# halfBridge.net
KiCad netlist of a schematic drawn in Altium Designer
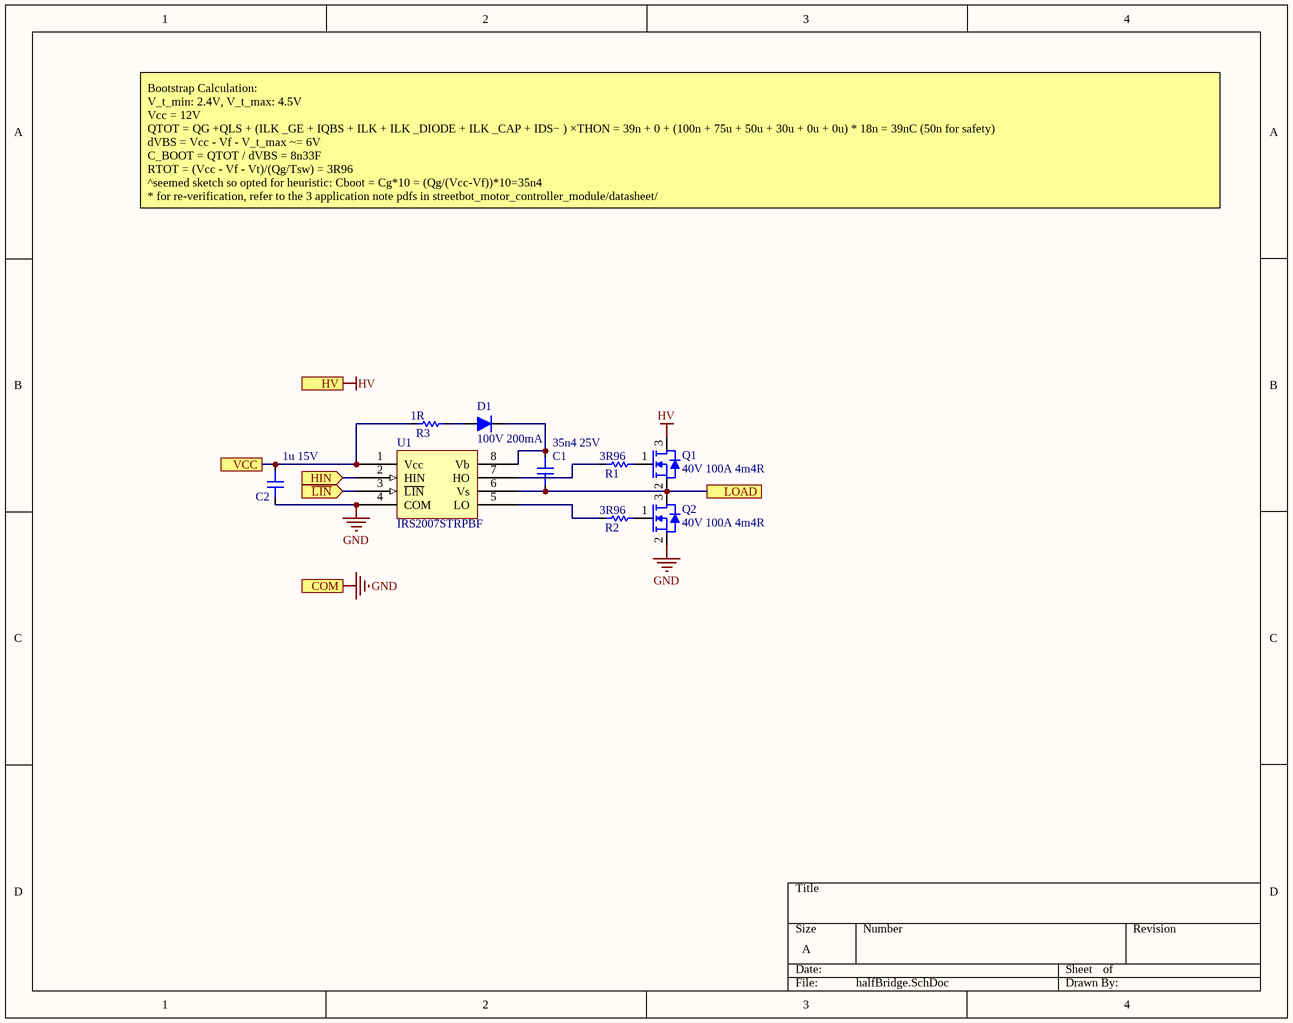
[diagram p0: halfBridge.SchDoc]

(export (version "E")
  (design (tool "Eeschema 10.0.6"))
  (components
    (comp (ref "C1")
      (value "35n4 25V")
      (footprint "CAP 0805 L")
      (description "CAP 0805")
      (libsource (lib "streetbot") (part "CAP 0805"))
    )
    (comp (ref "C2")
      (value "1u 15V")
      (footprint "CAP 0805 L")
      (description "CAP 0805")
      (libsource (lib "streetbot") (part "CAP 0805"))
    )
    (comp (ref "D1")
      (value "100V 200mA")
      (footprint "SODFL250X100-2M")
      (description "BAS16GWJ")
      (libsource (lib "streetbot") (part "DIODE 100V 200mA"))
    )
    (comp (ref "Q1")
      (value "40V 100A 4m4R")
      (footprint "DPAK127P600X120-5M (LFPAK56; Power-SO8)")
      (description "BUK7Y4R4-40EX")
      (libsource (lib "streetbot") (part "FET 40V 100A 4m4R"))
    )
    (comp (ref "Q2")
      (value "40V 100A 4m4R")
      (footprint "DPAK127P600X120-5M (LFPAK56; Power-SO8)")
      (description "BUK7Y4R4-40EX")
      (libsource (lib "streetbot") (part "FET 40V 100A 4m4R"))
    )
    (comp (ref "R1")
      (value "3R96")
      (footprint "RES 0603 L")
      (description "0603 RES")
      (libsource (lib "streetbot") (part "RES 0603"))
    )
    (comp (ref "R2")
      (value "3R96")
      (footprint "RES 0603 L")
      (description "0603 RES")
      (libsource (lib "streetbot") (part "RES 0603"))
    )
    (comp (ref "R3")
      (value "1R")
      (footprint "RES 0603 L")
      (description "0603 RES")
      (libsource (lib "streetbot") (part "RES 0603"))
    )
    (comp (ref "U1")
      (value "IRS2007STRPBF")
      (footprint "SOIC-8")
      (libsource (lib "streetbot") (part "IC Half Bridge Driver"))
    )
  )
  (nets
    (net (code "1") (name "/HIN") (class "Default")
      (node (ref "U1") (pin "2") (pinfunction "HIN_2") (pintype "input"))
    )
    (net (code "2") (name "/LOAD") (class "Default")
      (node (ref "C1") (pin "1") (pinfunction "1_1") (pintype "passive"))
      (node (ref "Q1") (pin "2") (pinfunction "2_2") (pintype "passive"))
      (node (ref "Q2") (pin "3") (pinfunction "3_3") (pintype "passive"))
      (node (ref "U1") (pin "6") (pinfunction "Vs_6") (pintype "passive"))
    )
    (net (code "3") (name "/VCC") (class "Default")
      (node (ref "C2") (pin "2") (pinfunction "2_2") (pintype "passive"))
      (node (ref "R3") (pin "1") (pinfunction "1_1") (pintype "passive"))
      (node (ref "U1") (pin "1") (pinfunction "Vcc_1") (pintype "power_in"))
    )
    (net (code "4") (name "/~{LIN}") (class "Default")
      (node (ref "U1") (pin "3") (pinfunction "~{LIN}_3") (pintype "input"))
    )
    (net (code "5") (name "GND") (class "Default")
      (node (ref "C2") (pin "1") (pinfunction "1_1") (pintype "passive"))
      (node (ref "Q2") (pin "2") (pinfunction "2_2") (pintype "passive"))
      (node (ref "U1") (pin "4") (pinfunction "COM_4") (pintype "power_in"))
    )
    (net (code "6") (name "HV") (class "Default")
      (node (ref "Q1") (pin "3") (pinfunction "3_3") (pintype "passive"))
    )
    (net (code "7") (name "Net-(D1-Pad1)") (class "Default")
      (node (ref "D1") (pin "1") (pinfunction "1_1") (pintype "passive"))
      (node (ref "R3") (pin "2") (pinfunction "2_2") (pintype "passive"))
    )
    (net (code "8") (name "Net-(Q1-14)") (class "Default")
      (node (ref "Q1") (pin "1") (pinfunction "14_1") (pintype "passive"))
      (node (ref "R1") (pin "2") (pinfunction "2_2") (pintype "passive"))
    )
    (net (code "9") (name "Net-(Q2-14)") (class "Default")
      (node (ref "Q2") (pin "1") (pinfunction "14_1") (pintype "passive"))
      (node (ref "R2") (pin "2") (pinfunction "2_2") (pintype "passive"))
    )
    (net (code "10") (name "Net-(U1-HO)") (class "Default")
      (node (ref "R1") (pin "1") (pinfunction "1_1") (pintype "passive"))
      (node (ref "U1") (pin "7") (pinfunction "HO_7") (pintype "passive"))
    )
    (net (code "11") (name "Net-(U1-LO)") (class "Default")
      (node (ref "R2") (pin "1") (pinfunction "1_1") (pintype "passive"))
      (node (ref "U1") (pin "5") (pinfunction "LO_5") (pintype "passive"))
    )
    (net (code "12") (name "Net-(U1-Vb)") (class "Default")
      (node (ref "C1") (pin "2") (pinfunction "2_2") (pintype "passive"))
      (node (ref "D1") (pin "2") (pinfunction "2_2") (pintype "passive"))
      (node (ref "U1") (pin "8") (pinfunction "Vb_8") (pintype "passive"))
    )
  )
)
